# Adafruit_ENS160.net
KiCad netlist of a schematic drawn in EAGLE
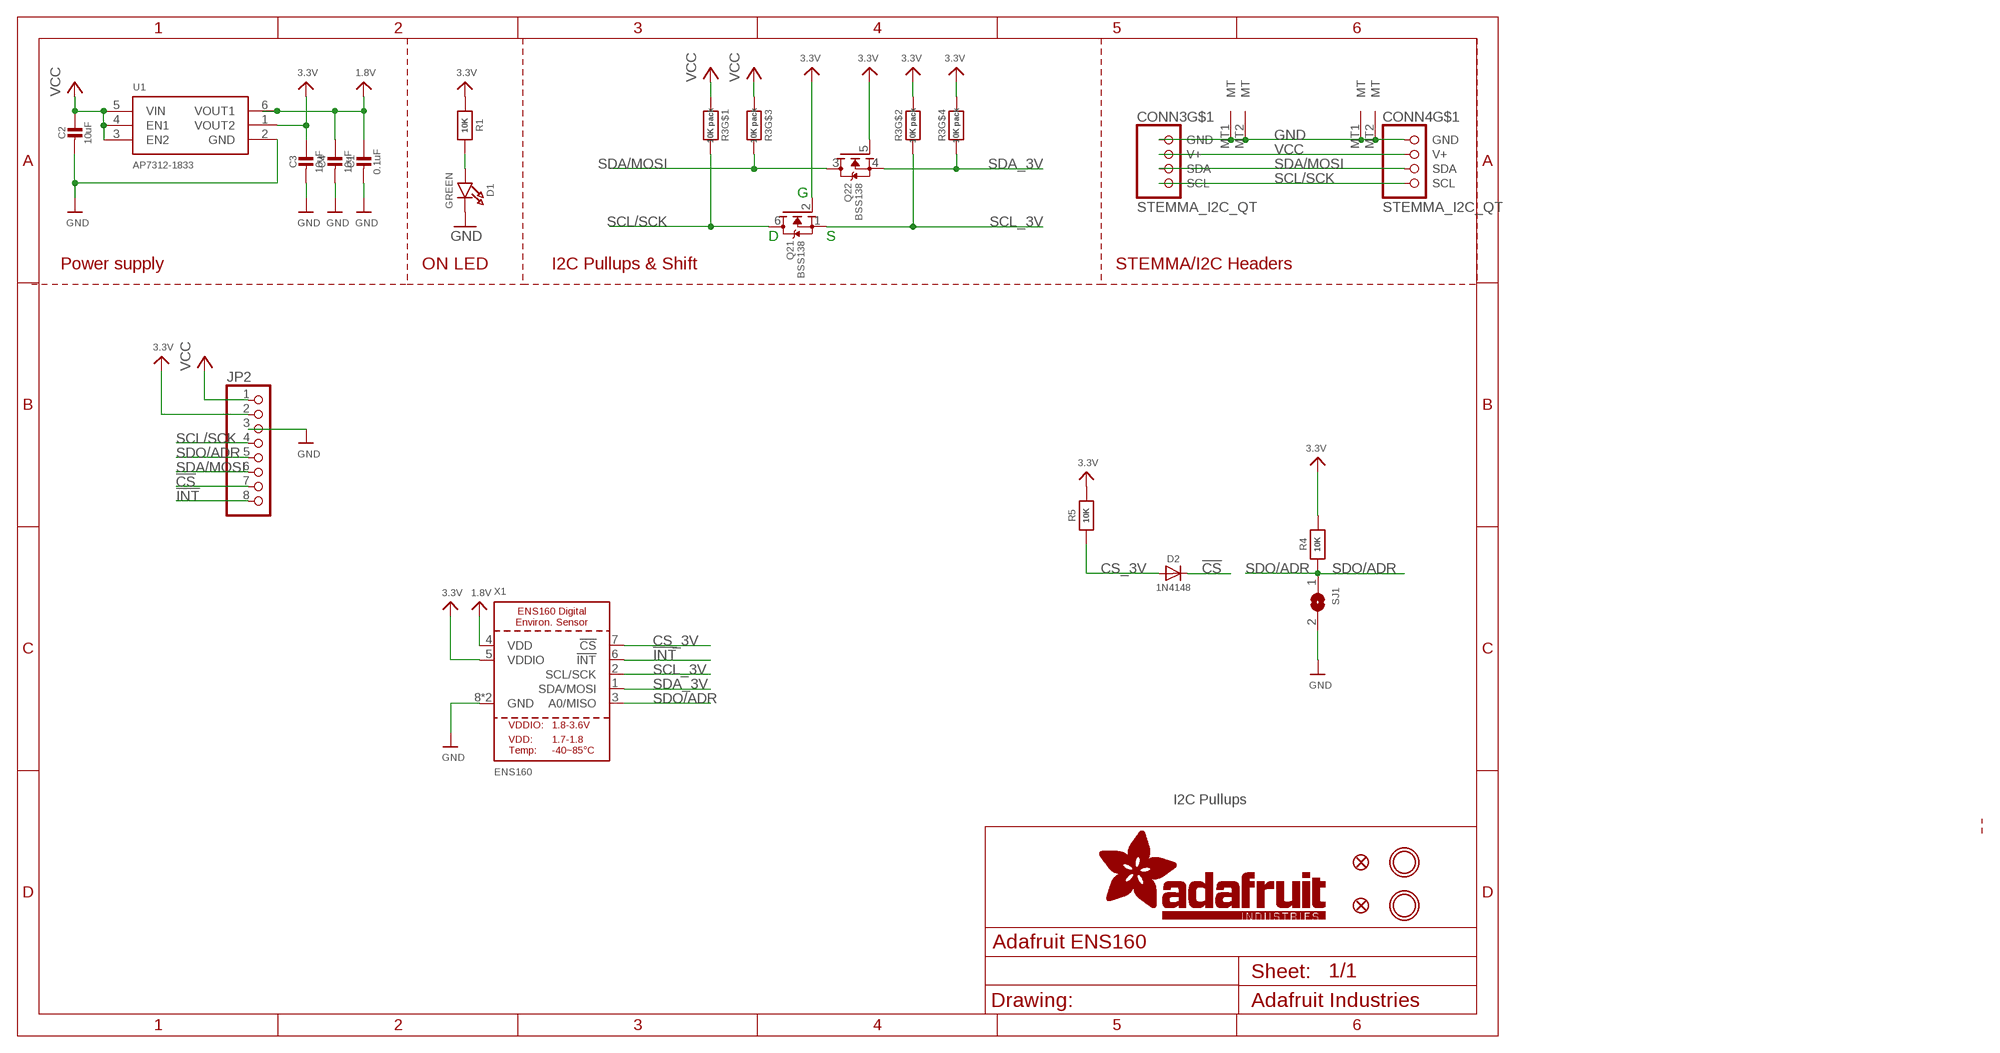
[diagram p0: schematic, sheet 1]

(export (version "E")
  (design (tool "Eeschema 10.0.6"))
  (components
    (comp (ref "C1")
      (value "0.1uF")
      (footprint "eagle-import:0603-NO")
      (libsource (lib "eagle-import") (part "CAP_CERAMIC0603_NO"))
    )
    (comp (ref "C2")
      (value "10uF")
      (footprint "eagle-import:0805-NO")
      (libsource (lib "eagle-import") (part "CAP_CERAMIC0805-NOOUTLINE"))
    )
    (comp (ref "C3")
      (value "10uF")
      (footprint "eagle-import:0805-NO")
      (libsource (lib "eagle-import") (part "CAP_CERAMIC0805-NOOUTLINE"))
    )
    (comp (ref "C4")
      (value "10uF")
      (footprint "eagle-import:0805-NO")
      (libsource (lib "eagle-import") (part "CAP_CERAMIC0805-NOOUTLINE"))
    )
    (comp (ref "CONN3")
      (value "STEMMA_I2C_QT")
      (footprint "eagle-import:JST_SH4")
      (libsource (lib "eagle-import") (part "STEMMA_I2C_QT"))
    )
    (comp (ref "CONN4")
      (value "STEMMA_I2C_QT")
      (footprint "eagle-import:JST_SH4")
      (libsource (lib "eagle-import") (part "STEMMA_I2C_QT"))
    )
    (comp (ref "D1")
      (value "GREEN")
      (footprint "eagle-import:CHIPLED_0603_NOOUTLINE")
      (libsource (lib "eagle-import") (part "LED0603_NOOUTLINE"))
    )
    (comp (ref "D2")
      (value "1N4148")
      (footprint "eagle-import:SOD-323")
      (libsource (lib "eagle-import") (part "DIODESOD-323"))
    )
    (comp (ref "FID3")
      (value "FIDUCIAL_1MM")
      (footprint "eagle-import:FIDUCIAL_1MM")
      (libsource (lib "eagle-import") (part "FIDUCIAL_1MM"))
    )
    (comp (ref "FID4")
      (value "FIDUCIAL_1MM")
      (footprint "eagle-import:FIDUCIAL_1MM")
      (libsource (lib "eagle-import") (part "FIDUCIAL_1MM"))
    )
    (comp (ref "JP2")
      (value "HEADER-1X870MIL")
      (footprint "eagle-import:1X08_ROUND_70")
      (libsource (lib "eagle-import") (part "HEADER-1X870MIL"))
    )
    (comp (ref "Q2")
      (value "BSS138")
      (footprint "eagle-import:SOT363")
      (libsource (lib "eagle-import") (part "MOSFET-N_DUAL"))
    )
    (comp (ref "R1")
      (value "10K")
      (footprint "eagle-import:0603-NO")
      (libsource (lib "eagle-import") (part "RESISTOR_0603_NOOUT"))
    )
    (comp (ref "R3")
      (value "10K pack")
      (footprint "eagle-import:RESPACK_4X0603")
      (libsource (lib "eagle-import") (part "RESISTOR_4PACK"))
    )
    (comp (ref "R4")
      (value "10K")
      (footprint "eagle-import:0603-NO")
      (libsource (lib "eagle-import") (part "RESISTOR_0603_NOOUT"))
    )
    (comp (ref "R5")
      (value "10K")
      (footprint "eagle-import:0603-NO")
      (libsource (lib "eagle-import") (part "RESISTOR_0603_NOOUT"))
    )
    (comp (ref "SJ1")
      (value "SOLDERJUMPER")
      (footprint "eagle-import:SOLDERJUMPER_ARROW_NOPASTE")
      (libsource (lib "eagle-import") (part "SOLDERJUMPER"))
    )
    (comp (ref "U$1")
      (value "MOUNTINGHOLE2.5")
      (footprint "eagle-import:MOUNTINGHOLE_2.5_PLATED")
      (libsource (lib "eagle-import") (part "MOUNTINGHOLE2.5"))
    )
    (comp (ref "U$17")
      (value "MOUNTINGHOLE2.5")
      (footprint "eagle-import:MOUNTINGHOLE_2.5_PLATED")
      (libsource (lib "eagle-import") (part "MOUNTINGHOLE2.5"))
    )
    (comp (ref "U1")
      (value "AP7312-1833")
      (footprint "eagle-import:SOT23-6")
      (libsource (lib "eagle-import") (part "VREG_SOT23-6_DUALAP7312"))
    )
    (comp (ref "X1")
      (value "ENS160")
      (footprint "eagle-import:ENS160")
      (libsource (lib "eagle-import") (part "ENS160"))
    )
  )
  (nets
    (net (code "1") (name "/CS_3V") (class "Default")
      (node (ref "D2") (pin "A") (pinfunction "A_A") (pintype "passive"))
      (node (ref "R5") (pin "1") (pinfunction "1_1") (pintype "passive"))
      (node (ref "X1") (pin "7") (pinfunction "~{CS}_7") (pintype "input"))
    )
    (net (code "2") (name "/SCL_3V") (class "Default")
      (node (ref "Q2") (pin "1") (pinfunction "S_1") (pintype "bidirectional"))
      (node (ref "R3") (pin "7") (pinfunction "2_7") (pintype "passive"))
      (node (ref "X1") (pin "2") (pinfunction "SCL/SCK_2") (pintype "input"))
    )
    (net (code "3") (name "/SCL{slash}SCK") (class "Default")
      (node (ref "CONN3") (pin "4") (pinfunction "SCL_4") (pintype "passive"))
      (node (ref "CONN4") (pin "4") (pinfunction "SCL_4") (pintype "passive"))
      (node (ref "JP2") (pin "4") (pinfunction "4_4") (pintype "passive"))
      (node (ref "Q2") (pin "6") (pinfunction "D_6") (pintype "bidirectional"))
      (node (ref "R3") (pin "8") (pinfunction "2_8") (pintype "passive"))
    )
    (net (code "4") (name "/SDA_3V") (class "Default")
      (node (ref "Q2") (pin "4") (pinfunction "S_4") (pintype "bidirectional"))
      (node (ref "R3") (pin "5") (pinfunction "2_5") (pintype "passive"))
      (node (ref "X1") (pin "1") (pinfunction "SDA/MOSI_1") (pintype "input"))
    )
    (net (code "5") (name "/SDA{slash}MOSI") (class "Default")
      (node (ref "CONN3") (pin "3") (pinfunction "SDA_3") (pintype "passive"))
      (node (ref "CONN4") (pin "3") (pinfunction "SDA_3") (pintype "passive"))
      (node (ref "JP2") (pin "6") (pinfunction "6_6") (pintype "passive"))
      (node (ref "Q2") (pin "3") (pinfunction "D_3") (pintype "bidirectional"))
      (node (ref "R3") (pin "6") (pinfunction "2_6") (pintype "passive"))
    )
    (net (code "6") (name "/SDO{slash}ADR") (class "Default")
      (node (ref "JP2") (pin "5") (pinfunction "5_5") (pintype "passive"))
      (node (ref "R4") (pin "1") (pinfunction "1_1") (pintype "passive"))
      (node (ref "SJ1") (pin "1") (pinfunction "1_1") (pintype "passive"))
      (node (ref "X1") (pin "3") (pinfunction "A0/MISO_3") (pintype "output"))
    )
    (net (code "7") (name "/~{CS}") (class "Default")
      (node (ref "D2") (pin "C") (pinfunction "C_C") (pintype "passive"))
      (node (ref "JP2") (pin "7") (pinfunction "7_7") (pintype "passive"))
    )
    (net (code "8") (name "/~{INT}") (class "Default")
      (node (ref "JP2") (pin "8") (pinfunction "8_8") (pintype "passive"))
      (node (ref "X1") (pin "6") (pinfunction "~{INT}_6") (pintype "output"))
    )
    (net (code "9") (name "1.8V") (class "Default")
      (node (ref "C1") (pin "1") (pinfunction "1_1") (pintype "passive"))
      (node (ref "C4") (pin "1") (pinfunction "1_1") (pintype "passive"))
      (node (ref "U1") (pin "6") (pinfunction "VOUT1_6") (pintype "bidirectional"))
      (node (ref "X1") (pin "4") (pinfunction "VDD_4") (pintype "power_in"))
    )
    (net (code "10") (name "3.3V") (class "Default")
      (node (ref "C3") (pin "1") (pinfunction "1_1") (pintype "passive"))
      (node (ref "JP2") (pin "2") (pinfunction "2_2") (pintype "passive"))
      (node (ref "Q2") (pin "2") (pinfunction "G_2") (pintype "bidirectional"))
      (node (ref "Q2") (pin "5") (pinfunction "G_5") (pintype "bidirectional"))
      (node (ref "R1") (pin "1") (pinfunction "1_1") (pintype "passive"))
      (node (ref "R3") (pin "2") (pinfunction "1_2") (pintype "passive"))
      (node (ref "R3") (pin "4") (pinfunction "1_4") (pintype "passive"))
      (node (ref "R4") (pin "2") (pinfunction "2_2") (pintype "passive"))
      (node (ref "R5") (pin "2") (pinfunction "2_2") (pintype "passive"))
      (node (ref "U1") (pin "1") (pinfunction "VOUT2_1") (pintype "bidirectional"))
      (node (ref "X1") (pin "5") (pinfunction "VDDIO_5") (pintype "power_in"))
    )
    (net (code "11") (name "GND") (class "Default")
      (node (ref "C1") (pin "2") (pinfunction "2_2") (pintype "passive"))
      (node (ref "C2") (pin "2") (pinfunction "2_2") (pintype "passive"))
      (node (ref "C3") (pin "2") (pinfunction "2_2") (pintype "passive"))
      (node (ref "C4") (pin "2") (pinfunction "2_2") (pintype "passive"))
      (node (ref "CONN3") (pin "1") (pinfunction "GND_1") (pintype "passive"))
      (node (ref "CONN3") (pin "MT1") (pinfunction "MT_MT1") (pintype "bidirectional"))
      (node (ref "CONN3") (pin "MT2") (pinfunction "MT_MT2") (pintype "bidirectional"))
      (node (ref "CONN4") (pin "1") (pinfunction "GND_1") (pintype "passive"))
      (node (ref "CONN4") (pin "MT1") (pinfunction "MT_MT1") (pintype "bidirectional"))
      (node (ref "CONN4") (pin "MT2") (pinfunction "MT_MT2") (pintype "bidirectional"))
      (node (ref "D1") (pin "C") (pinfunction "C_C") (pintype "passive"))
      (node (ref "JP2") (pin "3") (pinfunction "3_3") (pintype "passive"))
      (node (ref "SJ1") (pin "2") (pinfunction "2_2") (pintype "passive"))
      (node (ref "U1") (pin "2") (pinfunction "GND_2") (pintype "bidirectional"))
      (node (ref "X1") (pin "8") (pinfunction "GND_8") (pintype "power_in"))
      (node (ref "X1") (pin "9") (pinfunction "GND_9") (pintype "power_in"))
    )
    (net (code "12") (name "Net-(D1-PadA)") (class "Default")
      (node (ref "D1") (pin "A") (pinfunction "A_A") (pintype "passive"))
      (node (ref "R1") (pin "2") (pinfunction "2_2") (pintype "passive"))
    )
    (net (code "13") (name "VCC") (class "Default")
      (node (ref "C2") (pin "1") (pinfunction "1_1") (pintype "passive"))
      (node (ref "CONN3") (pin "2") (pinfunction "V+_2") (pintype "passive"))
      (node (ref "CONN4") (pin "2") (pinfunction "V+_2") (pintype "passive"))
      (node (ref "JP2") (pin "1") (pinfunction "1_1") (pintype "passive"))
      (node (ref "R3") (pin "1") (pinfunction "1_1") (pintype "passive"))
      (node (ref "R3") (pin "3") (pinfunction "1_3") (pintype "passive"))
      (node (ref "U1") (pin "3") (pinfunction "EN2_3") (pintype "bidirectional"))
      (node (ref "U1") (pin "4") (pinfunction "EN1_4") (pintype "bidirectional"))
      (node (ref "U1") (pin "5") (pinfunction "VIN_5") (pintype "bidirectional"))
    )
  )
)
